# 07-XORStatusLed.net
KiCad netlist of a schematic drawn in Altium Designer
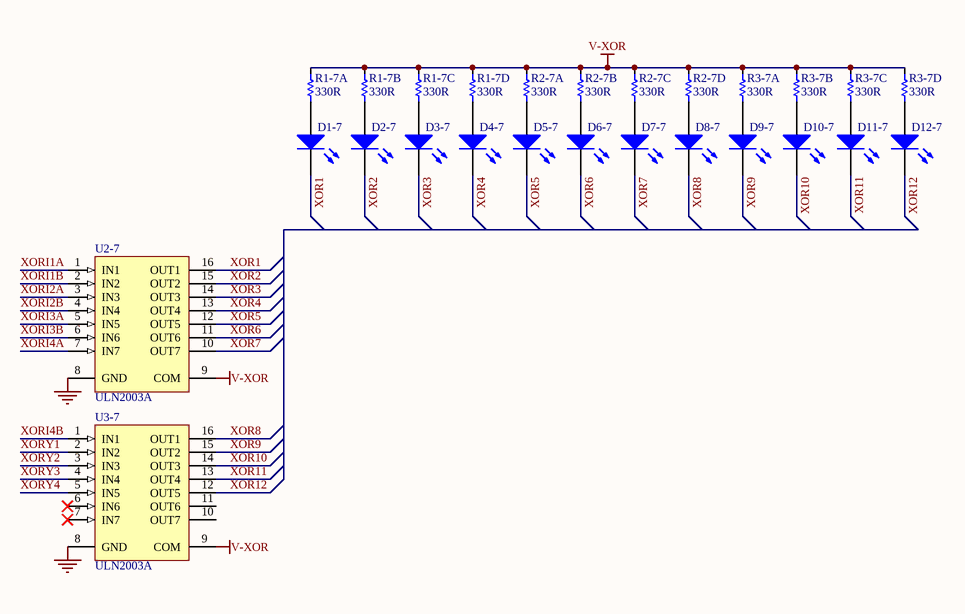
[diagram p0: 07-XORStatusLed.SchDoc]

(export (version "E")
  (design (tool "Eeschema 10.0.6"))
  (components
    (comp (ref "D1-7")
      (value "LED")
      (footprint "LED-0805")
      (description "Typical RED, GREEN, YELLOW, AMBER GaAs LED")
      (fields (field (name "PUBLISHER") "Altium Limited"))
      (libsource (lib "Miscellaneous Devices") (part "LED2"))
    )
    (comp (ref "D2-7")
      (value "LED")
      (footprint "LED-0805")
      (description "Typical RED, GREEN, YELLOW, AMBER GaAs LED")
      (fields (field (name "PUBLISHER") "Altium Limited"))
      (libsource (lib "Miscellaneous Devices") (part "LED2"))
    )
    (comp (ref "D3-7")
      (value "LED")
      (footprint "LED-0805")
      (description "Typical RED, GREEN, YELLOW, AMBER GaAs LED")
      (fields (field (name "PUBLISHER") "Altium Limited"))
      (libsource (lib "Miscellaneous Devices") (part "LED2"))
    )
    (comp (ref "D4-7")
      (value "LED")
      (footprint "LED-0805")
      (description "Typical RED, GREEN, YELLOW, AMBER GaAs LED")
      (fields (field (name "PUBLISHER") "Altium Limited"))
      (libsource (lib "Miscellaneous Devices") (part "LED2"))
    )
    (comp (ref "D5-7")
      (value "LED")
      (footprint "LED-0805")
      (description "Typical RED, GREEN, YELLOW, AMBER GaAs LED")
      (fields (field (name "PUBLISHER") "Altium Limited"))
      (libsource (lib "Miscellaneous Devices") (part "LED2"))
    )
    (comp (ref "D6-7")
      (value "LED")
      (footprint "LED-0805")
      (description "Typical RED, GREEN, YELLOW, AMBER GaAs LED")
      (fields (field (name "PUBLISHER") "Altium Limited"))
      (libsource (lib "Miscellaneous Devices") (part "LED2"))
    )
    (comp (ref "D7-7")
      (value "LED")
      (footprint "LED-0805")
      (description "Typical RED, GREEN, YELLOW, AMBER GaAs LED")
      (fields (field (name "PUBLISHER") "Altium Limited"))
      (libsource (lib "Miscellaneous Devices") (part "LED2"))
    )
    (comp (ref "D8-7")
      (value "LED")
      (footprint "LED-0805")
      (description "Typical RED, GREEN, YELLOW, AMBER GaAs LED")
      (fields (field (name "PUBLISHER") "Altium Limited"))
      (libsource (lib "Miscellaneous Devices") (part "LED2"))
    )
    (comp (ref "D9-7")
      (value "LED")
      (footprint "LED-0805")
      (description "Typical RED, GREEN, YELLOW, AMBER GaAs LED")
      (fields (field (name "PUBLISHER") "Altium Limited"))
      (libsource (lib "Miscellaneous Devices") (part "LED2"))
    )
    (comp (ref "D10-7")
      (value "LED")
      (footprint "LED-0805")
      (description "Typical RED, GREEN, YELLOW, AMBER GaAs LED")
      (fields (field (name "PUBLISHER") "Altium Limited"))
      (libsource (lib "Miscellaneous Devices") (part "LED2"))
    )
    (comp (ref "D11-7")
      (value "LED")
      (footprint "LED-0805")
      (description "Typical RED, GREEN, YELLOW, AMBER GaAs LED")
      (fields (field (name "PUBLISHER") "Altium Limited"))
      (libsource (lib "Miscellaneous Devices") (part "LED2"))
    )
    (comp (ref "D12-7")
      (value "LED")
      (footprint "LED-0805")
      (description "Typical RED, GREEN, YELLOW, AMBER GaAs LED")
      (fields (field (name "PUBLISHER") "Altium Limited"))
      (libsource (lib "Miscellaneous Devices") (part "LED2"))
    )
    (comp (ref "R1-7")
      (value "330R")
      (footprint "R-Array-0603-4")
      (description "RES ARRAY 4 RES 330 OHM 1206")
      (fields
        (field (name "DIGI-KEY PART NUMBER") "Y9331TR-ND")
        (field (name "MANUFACTURER") "Panasonic Electronic Components")
      )
      (libsource (lib "Dlib") (part "Res Array 4"))
    )
    (comp (ref "R2-7")
      (value "330R")
      (footprint "R-Array-0603-4")
      (description "RES ARRAY 4 RES 330 OHM 1206")
      (fields
        (field (name "DIGI-KEY PART NUMBER") "Y9331TR-ND")
        (field (name "MANUFACTURER") "Panasonic Electronic Components")
      )
      (libsource (lib "Dlib") (part "Res Array 4"))
    )
    (comp (ref "R3-7")
      (value "330R")
      (footprint "R-Array-0603-4")
      (description "RES ARRAY 4 RES 330 OHM 1206")
      (fields
        (field (name "DIGI-KEY PART NUMBER") "Y9331TR-ND")
        (field (name "MANUFACTURER") "Panasonic Electronic Components")
      )
      (libsource (lib "Dlib") (part "Res Array 4"))
    )
    (comp (ref "U2-7")
      (value "ULN2003A")
      (footprint "SOIC-16")
      (description "High-Voltage, High-Current Darlington Array")
      (fields (field (name "PUBLISHER") "Altium Limited"))
      (libsource (lib "Allegro Interface Darlington Driver") (part "ULN2003A"))
    )
    (comp (ref "U3-7")
      (value "ULN2003A")
      (footprint "SOIC-16")
      (description "High-Voltage, High-Current Darlington Array")
      (fields (field (name "PUBLISHER") "Altium Limited"))
      (libsource (lib "Allegro Interface Darlington Driver") (part "ULN2003A"))
    )
  )
  (nets
    (net (code "1") (name "/XOR1") (class "Default")
      (node (ref "D1-7") (pin "2") (pinfunction "K_2") (pintype "passive"))
      (node (ref "U2-7") (pin "16") (pinfunction "OUT1_16") (pintype "open_collector"))
    )
    (net (code "2") (name "/XOR2") (class "Default")
      (node (ref "D2-7") (pin "2") (pinfunction "K_2") (pintype "passive"))
      (node (ref "U2-7") (pin "15") (pinfunction "OUT2_15") (pintype "open_collector"))
    )
    (net (code "3") (name "/XOR3") (class "Default")
      (node (ref "D3-7") (pin "2") (pinfunction "K_2") (pintype "passive"))
      (node (ref "U2-7") (pin "14") (pinfunction "OUT3_14") (pintype "open_collector"))
    )
    (net (code "4") (name "/XOR4") (class "Default")
      (node (ref "D4-7") (pin "2") (pinfunction "K_2") (pintype "passive"))
      (node (ref "U2-7") (pin "13") (pinfunction "OUT4_13") (pintype "open_collector"))
    )
    (net (code "5") (name "/XOR5") (class "Default")
      (node (ref "D5-7") (pin "2") (pinfunction "K_2") (pintype "passive"))
      (node (ref "U2-7") (pin "12") (pinfunction "OUT5_12") (pintype "open_collector"))
    )
    (net (code "6") (name "/XOR6") (class "Default")
      (node (ref "D6-7") (pin "2") (pinfunction "K_2") (pintype "passive"))
      (node (ref "U2-7") (pin "11") (pinfunction "OUT6_11") (pintype "open_collector"))
    )
    (net (code "7") (name "/XOR7") (class "Default")
      (node (ref "D7-7") (pin "2") (pinfunction "K_2") (pintype "passive"))
      (node (ref "U2-7") (pin "10") (pinfunction "OUT7_10") (pintype "open_collector"))
    )
    (net (code "8") (name "/XOR8") (class "Default")
      (node (ref "D8-7") (pin "2") (pinfunction "K_2") (pintype "passive"))
      (node (ref "U3-7") (pin "16") (pinfunction "OUT1_16") (pintype "open_collector"))
    )
    (net (code "9") (name "/XOR9") (class "Default")
      (node (ref "D9-7") (pin "2") (pinfunction "K_2") (pintype "passive"))
      (node (ref "U3-7") (pin "15") (pinfunction "OUT2_15") (pintype "open_collector"))
    )
    (net (code "10") (name "/XOR10") (class "Default")
      (node (ref "D10-7") (pin "2") (pinfunction "K_2") (pintype "passive"))
      (node (ref "U3-7") (pin "14") (pinfunction "OUT3_14") (pintype "open_collector"))
    )
    (net (code "11") (name "/XOR11") (class "Default")
      (node (ref "D11-7") (pin "2") (pinfunction "K_2") (pintype "passive"))
      (node (ref "U3-7") (pin "13") (pinfunction "OUT4_13") (pintype "open_collector"))
    )
    (net (code "12") (name "/XOR12") (class "Default")
      (node (ref "D12-7") (pin "2") (pinfunction "K_2") (pintype "passive"))
      (node (ref "U3-7") (pin "12") (pinfunction "OUT5_12") (pintype "open_collector"))
    )
    (net (code "13") (name "/XORI1A") (class "Default")
      (node (ref "U2-7") (pin "1") (pinfunction "IN1_1") (pintype "input"))
    )
    (net (code "14") (name "/XORI1B") (class "Default")
      (node (ref "U2-7") (pin "2") (pinfunction "IN2_2") (pintype "input"))
    )
    (net (code "15") (name "/XORI2A") (class "Default")
      (node (ref "U2-7") (pin "3") (pinfunction "IN3_3") (pintype "input"))
    )
    (net (code "16") (name "/XORI2B") (class "Default")
      (node (ref "U2-7") (pin "4") (pinfunction "IN4_4") (pintype "input"))
    )
    (net (code "17") (name "/XORI3A") (class "Default")
      (node (ref "U2-7") (pin "5") (pinfunction "IN5_5") (pintype "input"))
    )
    (net (code "18") (name "/XORI3B") (class "Default")
      (node (ref "U2-7") (pin "6") (pinfunction "IN6_6") (pintype "input"))
    )
    (net (code "19") (name "/XORI4A") (class "Default")
      (node (ref "U2-7") (pin "7") (pinfunction "IN7_7") (pintype "input"))
    )
    (net (code "20") (name "/XORI4B") (class "Default")
      (node (ref "U3-7") (pin "1") (pinfunction "IN1_1") (pintype "input"))
    )
    (net (code "21") (name "/XORY1") (class "Default")
      (node (ref "U3-7") (pin "2") (pinfunction "IN2_2") (pintype "input"))
    )
    (net (code "22") (name "/XORY2") (class "Default")
      (node (ref "U3-7") (pin "3") (pinfunction "IN3_3") (pintype "input"))
    )
    (net (code "23") (name "/XORY3") (class "Default")
      (node (ref "U3-7") (pin "4") (pinfunction "IN4_4") (pintype "input"))
    )
    (net (code "24") (name "/XORY4") (class "Default")
      (node (ref "U3-7") (pin "5") (pinfunction "IN5_5") (pintype "input"))
    )
    (net (code "25") (name "GND") (class "Default")
      (node (ref "U2-7") (pin "8") (pinfunction "GND_8") (pintype "power_in"))
      (node (ref "U3-7") (pin "8") (pinfunction "GND_8") (pintype "power_in"))
    )
    (net (code "26") (name "Net-(D1-7-A)") (class "Default")
      (node (ref "D1-7") (pin "1") (pinfunction "A_1") (pintype "passive"))
      (node (ref "R1-7") (pin "1") (pinfunction "1_1") (pintype "passive"))
    )
    (net (code "27") (name "Net-(D2-7-A)") (class "Default")
      (node (ref "D2-7") (pin "1") (pinfunction "A_1") (pintype "passive"))
      (node (ref "R1-7") (pin "3") (pinfunction "1_3") (pintype "passive"))
    )
    (net (code "28") (name "Net-(D3-7-A)") (class "Default")
      (node (ref "D3-7") (pin "1") (pinfunction "A_1") (pintype "passive"))
      (node (ref "R1-7") (pin "5") (pinfunction "1_5") (pintype "passive"))
    )
    (net (code "29") (name "Net-(D4-7-A)") (class "Default")
      (node (ref "D4-7") (pin "1") (pinfunction "A_1") (pintype "passive"))
      (node (ref "R1-7") (pin "7") (pinfunction "1_7") (pintype "passive"))
    )
    (net (code "30") (name "Net-(D5-7-A)") (class "Default")
      (node (ref "D5-7") (pin "1") (pinfunction "A_1") (pintype "passive"))
      (node (ref "R2-7") (pin "1") (pinfunction "1_1") (pintype "passive"))
    )
    (net (code "31") (name "Net-(D6-7-A)") (class "Default")
      (node (ref "D6-7") (pin "1") (pinfunction "A_1") (pintype "passive"))
      (node (ref "R2-7") (pin "3") (pinfunction "1_3") (pintype "passive"))
    )
    (net (code "32") (name "Net-(D7-7-A)") (class "Default")
      (node (ref "D7-7") (pin "1") (pinfunction "A_1") (pintype "passive"))
      (node (ref "R2-7") (pin "5") (pinfunction "1_5") (pintype "passive"))
    )
    (net (code "33") (name "Net-(D8-7-A)") (class "Default")
      (node (ref "D8-7") (pin "1") (pinfunction "A_1") (pintype "passive"))
      (node (ref "R2-7") (pin "7") (pinfunction "1_7") (pintype "passive"))
    )
    (net (code "34") (name "Net-(D9-7-A)") (class "Default")
      (node (ref "D9-7") (pin "1") (pinfunction "A_1") (pintype "passive"))
      (node (ref "R3-7") (pin "1") (pinfunction "1_1") (pintype "passive"))
    )
    (net (code "35") (name "Net-(D10-7-A)") (class "Default")
      (node (ref "D10-7") (pin "1") (pinfunction "A_1") (pintype "passive"))
      (node (ref "R3-7") (pin "3") (pinfunction "1_3") (pintype "passive"))
    )
    (net (code "36") (name "Net-(D11-7-A)") (class "Default")
      (node (ref "D11-7") (pin "1") (pinfunction "A_1") (pintype "passive"))
      (node (ref "R3-7") (pin "5") (pinfunction "1_5") (pintype "passive"))
    )
    (net (code "37") (name "Net-(D12-7-A)") (class "Default")
      (node (ref "D12-7") (pin "1") (pinfunction "A_1") (pintype "passive"))
      (node (ref "R3-7") (pin "7") (pinfunction "1_7") (pintype "passive"))
    )
    (net (code "38") (name "V-XOR") (class "Default")
      (node (ref "R1-7") (pin "2") (pinfunction "2_2") (pintype "passive"))
      (node (ref "R1-7") (pin "4") (pinfunction "2_4") (pintype "passive"))
      (node (ref "R1-7") (pin "6") (pinfunction "2_6") (pintype "passive"))
      (node (ref "R1-7") (pin "8") (pinfunction "2_8") (pintype "passive"))
      (node (ref "R2-7") (pin "2") (pinfunction "2_2") (pintype "passive"))
      (node (ref "R2-7") (pin "4") (pinfunction "2_4") (pintype "passive"))
      (node (ref "R2-7") (pin "6") (pinfunction "2_6") (pintype "passive"))
      (node (ref "R2-7") (pin "8") (pinfunction "2_8") (pintype "passive"))
      (node (ref "R3-7") (pin "2") (pinfunction "2_2") (pintype "passive"))
      (node (ref "R3-7") (pin "4") (pinfunction "2_4") (pintype "passive"))
      (node (ref "R3-7") (pin "6") (pinfunction "2_6") (pintype "passive"))
      (node (ref "R3-7") (pin "8") (pinfunction "2_8") (pintype "passive"))
      (node (ref "U2-7") (pin "9") (pinfunction "COM_9") (pintype "passive"))
      (node (ref "U3-7") (pin "9") (pinfunction "COM_9") (pintype "passive"))
    )
    (net (code "39") (name "unconnected-(U3-7-IN6-Pad6)") (class "Default")
      (node (ref "U3-7") (pin "6") (pinfunction "IN6_6") (pintype "input+no_connect"))
    )
    (net (code "40") (name "unconnected-(U3-7-IN7-Pad7)") (class "Default")
      (node (ref "U3-7") (pin "7") (pinfunction "IN7_7") (pintype "input+no_connect"))
    )
    (net (code "41") (name "unconnected-(U3-7-OUT6-Pad11)") (class "Default")
      (node (ref "U3-7") (pin "11") (pinfunction "OUT6_11") (pintype "open_collector"))
    )
    (net (code "42") (name "unconnected-(U3-7-OUT7-Pad10)") (class "Default")
      (node (ref "U3-7") (pin "10") (pinfunction "OUT7_10") (pintype "open_collector"))
    )
  )
)
